# PF8_AudioOutput.net
KiCad netlist of a schematic drawn in Altium Designer
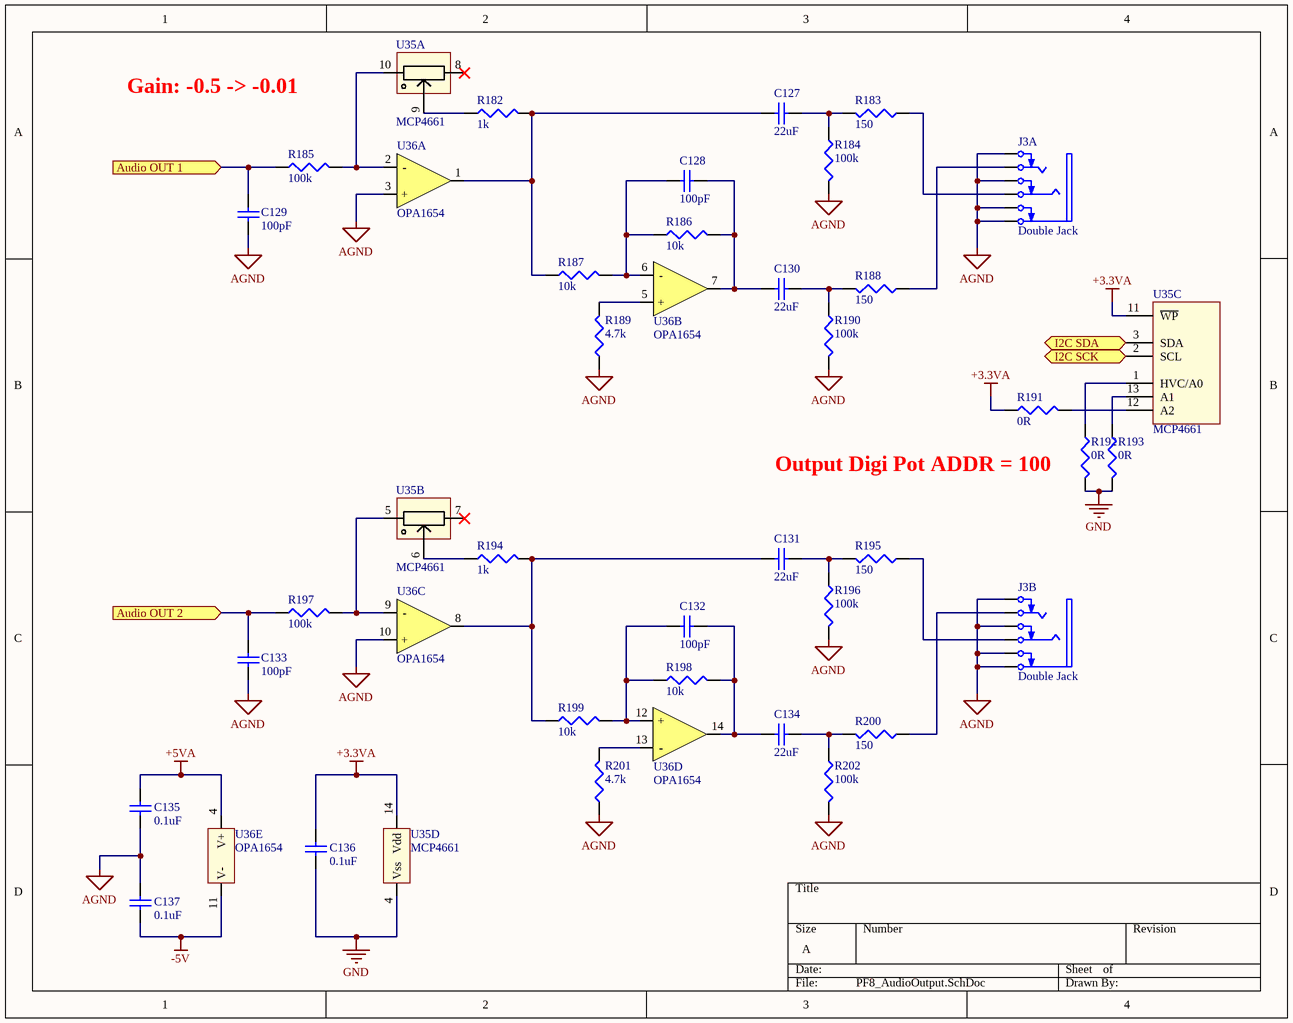
[diagram p0: PF8_AudioOutput.SchDoc]

(export (version "E")
  (design (tool "Eeschema 10.0.6"))
  (components
    (comp (ref "C127")
      (value "22uF")
      (footprint "CAP 0603 (1608 metric)")
      (description "Capacitor (Semiconductor SIM Model)")
      (libsource (lib "Miscellaneous Devices") (part "Cap Semi"))
    )
    (comp (ref "C128")
      (value "100pF")
      (footprint "CAP 0603 (1608 metric)")
      (description "Capacitor (Semiconductor SIM Model)")
      (libsource (lib "Miscellaneous Devices") (part "Cap Semi"))
    )
    (comp (ref "C129")
      (value "100pF")
      (footprint "CAP 0603 (1608 metric)")
      (description "Capacitor (Semiconductor SIM Model)")
      (libsource (lib "Miscellaneous Devices") (part "Cap Semi"))
    )
    (comp (ref "C130")
      (value "22uF")
      (footprint "CAP 0603 (1608 metric)")
      (description "Capacitor (Semiconductor SIM Model)")
      (libsource (lib "Miscellaneous Devices") (part "Cap Semi"))
    )
    (comp (ref "C131")
      (value "22uF")
      (footprint "CAP 0603 (1608 metric)")
      (description "Capacitor (Semiconductor SIM Model)")
      (libsource (lib "Miscellaneous Devices") (part "Cap Semi"))
    )
    (comp (ref "C132")
      (value "100pF")
      (footprint "CAP 0603 (1608 metric)")
      (description "Capacitor (Semiconductor SIM Model)")
      (libsource (lib "Miscellaneous Devices") (part "Cap Semi"))
    )
    (comp (ref "C133")
      (value "100pF")
      (footprint "CAP 0603 (1608 metric)")
      (description "Capacitor (Semiconductor SIM Model)")
      (libsource (lib "Miscellaneous Devices") (part "Cap Semi"))
    )
    (comp (ref "C134")
      (value "22uF")
      (footprint "CAP 0603 (1608 metric)")
      (description "Capacitor (Semiconductor SIM Model)")
      (libsource (lib "Miscellaneous Devices") (part "Cap Semi"))
    )
    (comp (ref "C135")
      (value "0.1uF")
      (footprint "C1206")
      (description "Capacitor (Semiconductor SIM Model)")
      (libsource (lib "Miscellaneous Devices") (part "Cap Semi"))
    )
    (comp (ref "C136")
      (value "0.1uF")
      (footprint "C1206")
      (description "Capacitor (Semiconductor SIM Model)")
      (libsource (lib "Miscellaneous Devices") (part "Cap Semi"))
    )
    (comp (ref "C137")
      (value "0.1uF")
      (footprint "C1206")
      (description "Capacitor (Semiconductor SIM Model)")
      (libsource (lib "Miscellaneous Devices") (part "Cap Semi"))
    )
    (comp (ref "J3")
      (value "Double Jack")
      (footprint "JACK/6-V4A")
      (description "Dual Jack stereo bypassed")
      (fields (field (name "PUBLISHER") "Altium Limited"))
      (libsource (lib "") (part "Dual TRS Jack Bypassed_1"))
    )
    (comp (ref "R182")
      (value "1k")
      (footprint "RES 0603 (1608 metric)")
      (description "Resistor")
      (libsource (lib "Miscellaneous Devices") (part "Res3"))
    )
    (comp (ref "R183")
      (value "150")
      (footprint "RES 0603 (1608 metric)")
      (description "Resistor")
      (libsource (lib "Miscellaneous Devices") (part "Res3"))
    )
    (comp (ref "R184")
      (value "100k")
      (footprint "RES 0603 (1608 metric)")
      (description "Resistor")
      (libsource (lib "Miscellaneous Devices") (part "Res3"))
    )
    (comp (ref "R185")
      (value "100k")
      (footprint "RES 0603 (1608 metric)")
      (description "Resistor")
      (libsource (lib "Miscellaneous Devices") (part "Res3"))
    )
    (comp (ref "R186")
      (value "10k")
      (footprint "RES 0603 (1608 metric)")
      (description "Resistor")
      (libsource (lib "Miscellaneous Devices") (part "Res3"))
    )
    (comp (ref "R187")
      (value "10k")
      (footprint "RES 0603 (1608 metric)")
      (description "Resistor")
      (libsource (lib "Miscellaneous Devices") (part "Res3"))
    )
    (comp (ref "R188")
      (value "150")
      (footprint "RES 0603 (1608 metric)")
      (description "Resistor")
      (libsource (lib "Miscellaneous Devices") (part "Res3"))
    )
    (comp (ref "R189")
      (value "4.7k")
      (footprint "RES 0603 (1608 metric)")
      (description "Resistor")
      (libsource (lib "Miscellaneous Devices") (part "Res3"))
    )
    (comp (ref "R190")
      (value "100k")
      (footprint "RES 0603 (1608 metric)")
      (description "Resistor")
      (libsource (lib "Miscellaneous Devices") (part "Res3"))
    )
    (comp (ref "R191")
      (value "0R")
      (footprint "RES 0603 (1608 metric)")
      (description "Resistor")
      (libsource (lib "Miscellaneous Devices") (part "Res3"))
    )
    (comp (ref "R192")
      (value "0R")
      (footprint "RES 0603 (1608 metric)")
      (description "Resistor")
      (libsource (lib "Miscellaneous Devices") (part "Res3"))
    )
    (comp (ref "R193")
      (value "0R")
      (footprint "RES 0603 (1608 metric)")
      (description "Resistor")
      (libsource (lib "Miscellaneous Devices") (part "Res3"))
    )
    (comp (ref "R194")
      (value "1k")
      (footprint "RES 0603 (1608 metric)")
      (description "Resistor")
      (libsource (lib "Miscellaneous Devices") (part "Res3"))
    )
    (comp (ref "R195")
      (value "150")
      (footprint "RES 0603 (1608 metric)")
      (description "Resistor")
      (libsource (lib "Miscellaneous Devices") (part "Res3"))
    )
    (comp (ref "R196")
      (value "100k")
      (footprint "RES 0603 (1608 metric)")
      (description "Resistor")
      (libsource (lib "Miscellaneous Devices") (part "Res3"))
    )
    (comp (ref "R197")
      (value "100k")
      (footprint "RES 0603 (1608 metric)")
      (description "Resistor")
      (libsource (lib "Miscellaneous Devices") (part "Res3"))
    )
    (comp (ref "R198")
      (value "10k")
      (footprint "RES 0603 (1608 metric)")
      (description "Resistor")
      (libsource (lib "Miscellaneous Devices") (part "Res3"))
    )
    (comp (ref "R199")
      (value "10k")
      (footprint "RES 0603 (1608 metric)")
      (description "Resistor")
      (libsource (lib "Miscellaneous Devices") (part "Res3"))
    )
    (comp (ref "R200")
      (value "150")
      (footprint "RES 0603 (1608 metric)")
      (description "Resistor")
      (libsource (lib "Miscellaneous Devices") (part "Res3"))
    )
    (comp (ref "R201")
      (value "4.7k")
      (footprint "RES 0603 (1608 metric)")
      (description "Resistor")
      (libsource (lib "Miscellaneous Devices") (part "Res3"))
    )
    (comp (ref "R202")
      (value "100k")
      (footprint "RES 0603 (1608 metric)")
      (description "Resistor")
      (libsource (lib "Miscellaneous Devices") (part "Res3"))
    )
    (comp (ref "U35")
      (value "MCP4661")
      (footprint "TSSOP14_MC")
      (description "Dual DigiPot non volatile I2C")
      (libsource (lib "") (part "MCP4661_1"))
    )
    (comp (ref "U36")
      (value "OPA1654")
      (footprint "D14")
      (description "Quad Audio OpAmp")
      (libsource (lib "Michel") (part "OPA1654"))
    )
  )
  (nets
    (net (code "1") (name "+3.3VA") (class "Default")
      (node (ref "C136") (pin "1") (pinfunction "1_1") (pintype "passive"))
      (node (ref "R191") (pin "1") (pinfunction "1_1") (pintype "passive"))
      (node (ref "U35") (pin "11") (pinfunction "~{WP}_11") (pintype "passive"))
      (node (ref "U35") (pin "14") (pinfunction "Vdd_14") (pintype "power_in"))
    )
    (net (code "2") (name "+5VA") (class "Default")
      (node (ref "C135") (pin "1") (pinfunction "1_1") (pintype "passive"))
      (node (ref "U36") (pin "4") (pinfunction "V+_4") (pintype "power_in"))
    )
    (net (code "3") (name "-5V") (class "Default")
      (node (ref "C137") (pin "2") (pinfunction "2_2") (pintype "passive"))
      (node (ref "U36") (pin "11") (pinfunction "V-_11") (pintype "power_in"))
    )
    (net (code "4") (name "/Audio OUT 1") (class "Default")
      (node (ref "C129") (pin "2") (pinfunction "2_2") (pintype "passive"))
      (node (ref "R185") (pin "1") (pinfunction "1_1") (pintype "passive"))
    )
    (net (code "5") (name "/Audio OUT 2") (class "Default")
      (node (ref "C133") (pin "2") (pinfunction "2_2") (pintype "passive"))
      (node (ref "R197") (pin "1") (pinfunction "1_1") (pintype "passive"))
    )
    (net (code "6") (name "/I2C SCK") (class "Default")
      (node (ref "U35") (pin "2") (pinfunction "SCL_2") (pintype "passive"))
    )
    (net (code "7") (name "/I2C SDA") (class "Default")
      (node (ref "U35") (pin "3") (pinfunction "SDA_3") (pintype "passive"))
    )
    (net (code "8") (name "AGND") (class "Default")
      (node (ref "C129") (pin "1") (pinfunction "1_1") (pintype "passive"))
      (node (ref "C133") (pin "1") (pinfunction "1_1") (pintype "passive"))
      (node (ref "C135") (pin "2") (pinfunction "2_2") (pintype "passive"))
      (node (ref "C137") (pin "1") (pinfunction "1_1") (pintype "passive"))
      (node (ref "J3") (pin "1") (pinfunction "SB_1") (pintype "passive"))
      (node (ref "J3") (pin "10") (pinfunction "S_10") (pintype "power_in"))
      (node (ref "J3") (pin "2") (pinfunction "RB_2") (pintype "passive"))
      (node (ref "J3") (pin "3") (pinfunction "TB_3") (pintype "passive"))
      (node (ref "J3") (pin "4") (pinfunction "S_4") (pintype "power_in"))
      (node (ref "J3") (pin "7") (pinfunction "SB_7") (pintype "passive"))
      (node (ref "J3") (pin "8") (pinfunction "RB_8") (pintype "passive"))
      (node (ref "J3") (pin "9") (pinfunction "TB_9") (pintype "passive"))
      (node (ref "R184") (pin "2") (pinfunction "2_2") (pintype "passive"))
      (node (ref "R189") (pin "1") (pinfunction "1_1") (pintype "passive"))
      (node (ref "R190") (pin "2") (pinfunction "2_2") (pintype "passive"))
      (node (ref "R196") (pin "2") (pinfunction "2_2") (pintype "passive"))
      (node (ref "R201") (pin "1") (pinfunction "1_1") (pintype "passive"))
      (node (ref "R202") (pin "2") (pinfunction "2_2") (pintype "passive"))
      (node (ref "U36") (pin "10") (pinfunction "+_10") (pintype "passive"))
      (node (ref "U36") (pin "3") (pinfunction "+_3") (pintype "passive"))
    )
    (net (code "9") (name "GND") (class "Default")
      (node (ref "C136") (pin "2") (pinfunction "2_2") (pintype "passive"))
      (node (ref "R192") (pin "2") (pinfunction "2_2") (pintype "passive"))
      (node (ref "R193") (pin "2") (pinfunction "2_2") (pintype "passive"))
      (node (ref "U35") (pin "4") (pinfunction "Vss_4") (pintype "power_in"))
    )
    (net (code "10") (name "Net-(C127-Pad1)") (class "Default")
      (node (ref "C127") (pin "1") (pinfunction "1_1") (pintype "passive"))
      (node (ref "R183") (pin "2") (pinfunction "2_2") (pintype "passive"))
      (node (ref "R184") (pin "1") (pinfunction "1_1") (pintype "passive"))
    )
    (net (code "11") (name "Net-(C130-Pad1)") (class "Default")
      (node (ref "C130") (pin "1") (pinfunction "1_1") (pintype "passive"))
      (node (ref "R188") (pin "2") (pinfunction "2_2") (pintype "passive"))
      (node (ref "R190") (pin "1") (pinfunction "1_1") (pintype "passive"))
    )
    (net (code "12") (name "Net-(C131-Pad1)") (class "Default")
      (node (ref "C131") (pin "1") (pinfunction "1_1") (pintype "passive"))
      (node (ref "R195") (pin "2") (pinfunction "2_2") (pintype "passive"))
      (node (ref "R196") (pin "1") (pinfunction "1_1") (pintype "passive"))
    )
    (net (code "13") (name "Net-(C134-Pad1)") (class "Default")
      (node (ref "C134") (pin "1") (pinfunction "1_1") (pintype "passive"))
      (node (ref "R200") (pin "2") (pinfunction "2_2") (pintype "passive"))
      (node (ref "R202") (pin "1") (pinfunction "1_1") (pintype "passive"))
    )
    (net (code "14") (name "Net-(J3A-R)") (class "Default")
      (node (ref "J3") (pin "11") (pinfunction "R_11") (pintype "passive"))
      (node (ref "R183") (pin "1") (pinfunction "1_1") (pintype "passive"))
    )
    (net (code "15") (name "Net-(J3A-T)") (class "Default")
      (node (ref "J3") (pin "12") (pinfunction "T_12") (pintype "passive"))
      (node (ref "R188") (pin "1") (pinfunction "1_1") (pintype "passive"))
    )
    (net (code "16") (name "Net-(J3B-R)") (class "Default")
      (node (ref "J3") (pin "5") (pinfunction "R_5") (pintype "passive"))
      (node (ref "R195") (pin "1") (pinfunction "1_1") (pintype "passive"))
    )
    (net (code "17") (name "Net-(J3B-T)") (class "Default")
      (node (ref "J3") (pin "6") (pinfunction "T_6") (pintype "passive"))
      (node (ref "R200") (pin "1") (pinfunction "1_1") (pintype "passive"))
    )
    (net (code "18") (name "Net-(U35A-P0B)") (class "Default")
      (node (ref "R185") (pin "2") (pinfunction "2_2") (pintype "passive"))
      (node (ref "U35") (pin "10") (pinfunction "P0B_10") (pintype "passive"))
      (node (ref "U36") (pin "2") (pinfunction "-_2") (pintype "passive"))
    )
    (net (code "19") (name "Net-(U35A-P0W)") (class "Default")
      (node (ref "R182") (pin "1") (pinfunction "1_1") (pintype "passive"))
      (node (ref "U35") (pin "9") (pinfunction "P0W_9") (pintype "passive"))
    )
    (net (code "20") (name "Net-(U35B-P1B)") (class "Default")
      (node (ref "R197") (pin "2") (pinfunction "2_2") (pintype "passive"))
      (node (ref "U35") (pin "5") (pinfunction "P1B_5") (pintype "passive"))
      (node (ref "U36") (pin "9") (pinfunction "-_9") (pintype "passive"))
    )
    (net (code "21") (name "Net-(U35B-P1W)") (class "Default")
      (node (ref "R194") (pin "1") (pinfunction "1_1") (pintype "passive"))
      (node (ref "U35") (pin "6") (pinfunction "P1W_6") (pintype "passive"))
    )
    (net (code "22") (name "Net-(U35C-A1)") (class "Default")
      (node (ref "R193") (pin "1") (pinfunction "1_1") (pintype "passive"))
      (node (ref "U35") (pin "13") (pinfunction "A1_13") (pintype "power_in"))
    )
    (net (code "23") (name "Net-(U35C-A2)") (class "Default")
      (node (ref "R191") (pin "2") (pinfunction "2_2") (pintype "passive"))
      (node (ref "U35") (pin "12") (pinfunction "A2_12") (pintype "power_in"))
    )
    (net (code "24") (name "Net-(U35C-HVC{slash}A0)") (class "Default")
      (node (ref "R192") (pin "1") (pinfunction "1_1") (pintype "passive"))
      (node (ref "U35") (pin "1") (pinfunction "HVC/A0_1") (pintype "power_in"))
    )
    (net (code "25") (name "Net-(U36A-OUT)") (class "Default")
      (node (ref "C127") (pin "2") (pinfunction "2_2") (pintype "passive"))
      (node (ref "R182") (pin "2") (pinfunction "2_2") (pintype "passive"))
      (node (ref "R187") (pin "1") (pinfunction "1_1") (pintype "passive"))
      (node (ref "U36") (pin "1") (pinfunction "OUT_1") (pintype "passive"))
    )
    (net (code "26") (name "Net-(U36B-+)") (class "Default")
      (node (ref "R189") (pin "2") (pinfunction "2_2") (pintype "passive"))
      (node (ref "U36") (pin "5") (pinfunction "+_5") (pintype "passive"))
    )
    (net (code "27") (name "Net-(U36B--)") (class "Default")
      (node (ref "C128") (pin "2") (pinfunction "2_2") (pintype "passive"))
      (node (ref "R186") (pin "1") (pinfunction "1_1") (pintype "passive"))
      (node (ref "R187") (pin "2") (pinfunction "2_2") (pintype "passive"))
      (node (ref "U36") (pin "6") (pinfunction "-_6") (pintype "passive"))
    )
    (net (code "28") (name "Net-(U36B-OUT)") (class "Default")
      (node (ref "C128") (pin "1") (pinfunction "1_1") (pintype "passive"))
      (node (ref "C130") (pin "2") (pinfunction "2_2") (pintype "passive"))
      (node (ref "R186") (pin "2") (pinfunction "2_2") (pintype "passive"))
      (node (ref "U36") (pin "7") (pinfunction "OUT_7") (pintype "passive"))
    )
    (net (code "29") (name "Net-(U36C-OUT)") (class "Default")
      (node (ref "C131") (pin "2") (pinfunction "2_2") (pintype "passive"))
      (node (ref "R194") (pin "2") (pinfunction "2_2") (pintype "passive"))
      (node (ref "R199") (pin "1") (pinfunction "1_1") (pintype "passive"))
      (node (ref "U36") (pin "8") (pinfunction "OUT_8") (pintype "passive"))
    )
    (net (code "30") (name "Net-(U36D-+)") (class "Default")
      (node (ref "C132") (pin "2") (pinfunction "2_2") (pintype "passive"))
      (node (ref "R198") (pin "1") (pinfunction "1_1") (pintype "passive"))
      (node (ref "R199") (pin "2") (pinfunction "2_2") (pintype "passive"))
      (node (ref "U36") (pin "12") (pinfunction "+_12") (pintype "passive"))
    )
    (net (code "31") (name "Net-(U36D--)") (class "Default")
      (node (ref "R201") (pin "2") (pinfunction "2_2") (pintype "passive"))
      (node (ref "U36") (pin "13") (pinfunction "-_13") (pintype "passive"))
    )
    (net (code "32") (name "Net-(U36D-OUT)") (class "Default")
      (node (ref "C132") (pin "1") (pinfunction "1_1") (pintype "passive"))
      (node (ref "C134") (pin "2") (pinfunction "2_2") (pintype "passive"))
      (node (ref "R198") (pin "2") (pinfunction "2_2") (pintype "passive"))
      (node (ref "U36") (pin "14") (pinfunction "OUT_14") (pintype "passive"))
    )
    (net (code "33") (name "unconnected-(U35A-P0A-Pad8)") (class "Default")
      (node (ref "U35") (pin "8") (pinfunction "P0A_8") (pintype "passive+no_connect"))
    )
    (net (code "34") (name "unconnected-(U35B-P1A-Pad7)") (class "Default")
      (node (ref "U35") (pin "7") (pinfunction "P1A_7") (pintype "passive+no_connect"))
    )
  )
)
